# 8_SATA_TFCARD.net
KiCad netlist of a schematic drawn in Altium Designer
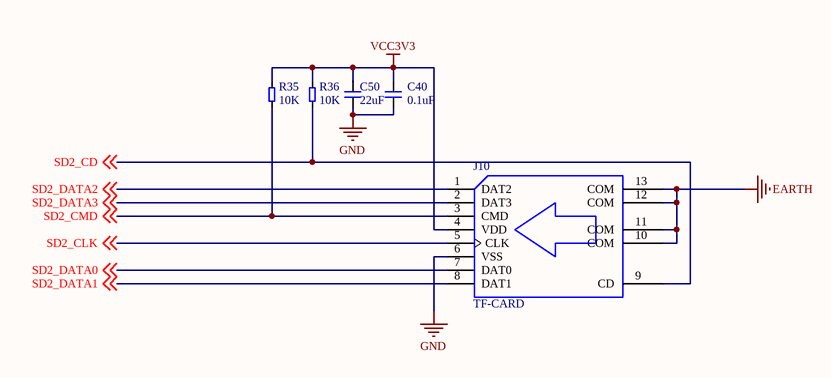
[diagram p0: 8.SATA&TFCARD.SchDoc]

(export (version "E")
  (design (tool "Eeschema 10.0.6"))
  (components
    (comp (ref "C40")
      (value "0.1uF")
      (footprint "0603C")
      (description "电容")
      (libsource (lib "*") (part "电容"))
    )
    (comp (ref "C50") (value "22uF") (footprint "0603C") (description "电容") (libsource (lib "*") (part "电容")))
    (comp (ref "J10") (value "TF-CARD") (footprint "TF-CARD") (libsource (lib "LDT-SCH") (part "TF-CARD")))
    (comp (ref "R35")
      (value "10K")
      (footprint "0603R")
      (description "电阻")
      (libsource (lib "LDT-SCH") (part "电阻"))
    )
    (comp (ref "R36")
      (value "10K")
      (footprint "0603R")
      (description "电阻")
      (libsource (lib "LDT-SCH") (part "电阻"))
    )
  )
  (nets
    (net (code "1") (name "EARTH") (class "Default")
      (node (ref "J10") (pin "10") (pinfunction "COM_10") (pintype "passive"))
      (node (ref "J10") (pin "11") (pinfunction "COM_11") (pintype "passive"))
      (node (ref "J10") (pin "12") (pinfunction "COM_12") (pintype "passive"))
      (node (ref "J10") (pin "13") (pinfunction "COM_13") (pintype "passive"))
    )
    (net (code "2") (name "GND") (class "Default")
      (node (ref "C40") (pin "1") (pintype "passive"))
      (node (ref "C50") (pin "1") (pintype "passive"))
      (node (ref "J10") (pin "6") (pinfunction "VSS_6") (pintype "passive"))
    )
    (net (code "3") (name "SD2_CD") (class "Default")
      (node (ref "J10") (pin "9") (pinfunction "CD_9") (pintype "passive"))
      (node (ref "R36") (pin "1") (pintype "passive"))
    )
    (net (code "4") (name "SD2_CLK") (class "Default")
      (node (ref "J10") (pin "5") (pinfunction "CLK_5") (pintype "passive"))
    )
    (net (code "5") (name "SD2_CMD") (class "Default")
      (node (ref "J10") (pin "3") (pinfunction "CMD_3") (pintype "passive"))
      (node (ref "R35") (pin "1") (pintype "passive"))
    )
    (net (code "6") (name "SD2_DATA0") (class "Default")
      (node (ref "J10") (pin "7") (pinfunction "DAT0_7") (pintype "passive"))
    )
    (net (code "7") (name "SD2_DATA1") (class "Default")
      (node (ref "J10") (pin "8") (pinfunction "DAT1_8") (pintype "passive"))
    )
    (net (code "8") (name "SD2_DATA2") (class "Default")
      (node (ref "J10") (pin "1") (pinfunction "DAT2_1") (pintype "passive"))
    )
    (net (code "9") (name "SD2_DATA3") (class "Default")
      (node (ref "J10") (pin "2") (pinfunction "DAT3_2") (pintype "passive"))
    )
    (net (code "10") (name "VCC3V3") (class "Default")
      (node (ref "C40") (pin "2") (pintype "passive"))
      (node (ref "C50") (pin "2") (pintype "passive"))
      (node (ref "J10") (pin "4") (pinfunction "VDD_4") (pintype "passive"))
      (node (ref "R35") (pin "2") (pintype "passive"))
      (node (ref "R36") (pin "2") (pintype "passive"))
    )
  )
)
